# SignalProcessing.net
KiCad netlist of a schematic drawn in Altium Designer
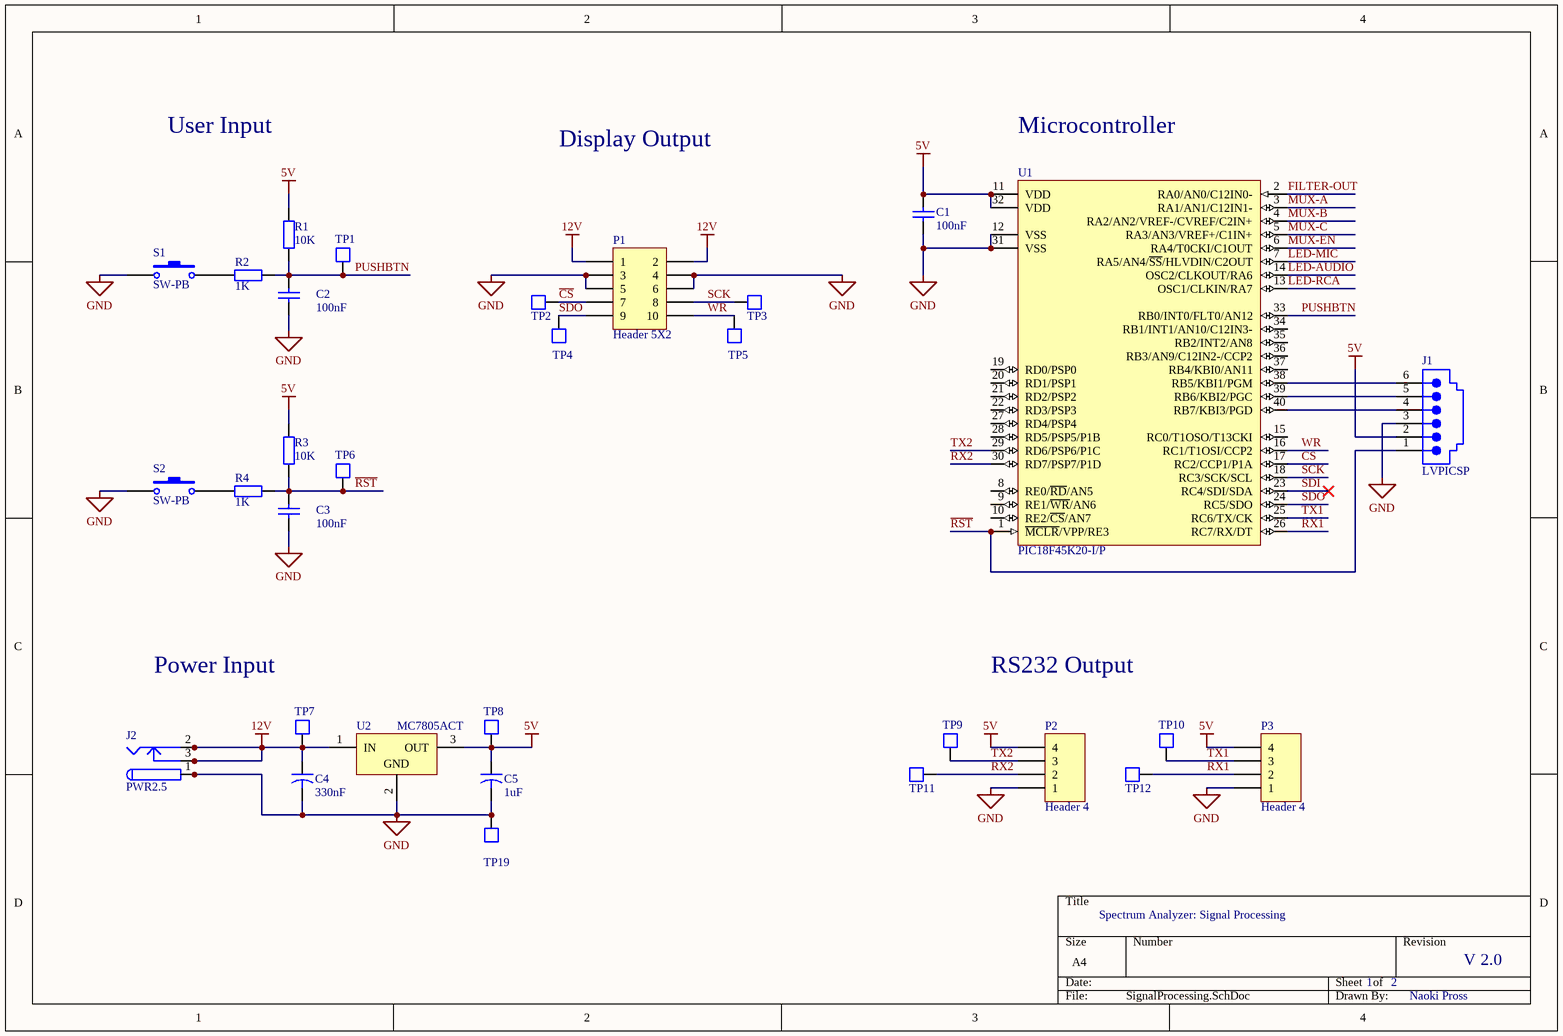
[diagram p0: SignalProcessing.SchDoc]

(export (version "E")
  (design (tool "Eeschema 10.0.6"))
  (components
    (comp (ref "C1")
      (value "100nF")
      (footprint "RAD-0.1")
      (description "Capacitor")
      (fields (field (name "Comment") "Cap") (field (name "PUBLISHER") "Altium Limited"))
      (libsource (lib "Miscellaneous Devices") (part "Cap"))
    )
    (comp (ref "C2")
      (value "100nF")
      (footprint "RAD-0.1")
      (description "Capacitor")
      (fields (field (name "Comment") "Cap") (field (name "PUBLISHER") "Altium Limited"))
      (libsource (lib "Miscellaneous Devices") (part "Cap"))
    )
    (comp (ref "C3")
      (value "100nF")
      (footprint "RAD-0.1")
      (description "Capacitor")
      (fields (field (name "Comment") "Cap") (field (name "PUBLISHER") "Altium Limited"))
      (libsource (lib "Miscellaneous Devices") (part "Cap"))
    )
    (comp (ref "C4")
      (value "330nF")
      (footprint "CAPR5-4X5")
      (description "Capacitor")
      (fields (field (name "Comment") "Cap2") (field (name "PUBLISHER") "Altium Limited"))
      (libsource (lib "Miscellaneous Devices") (part "Cap2"))
    )
    (comp (ref "C5")
      (value "1uF")
      (footprint "CAPR5-4X5")
      (description "Capacitor")
      (fields (field (name "Comment") "Cap2") (field (name "PUBLISHER") "Altium Limited"))
      (libsource (lib "Miscellaneous Devices") (part "Cap2"))
    )
    (comp (ref "J1")
      (value "LVPICSP")
      (footprint "95001-2661")
      (description "Right Angle, Low Profile, Flangeless PCB Jack")
      (fields (field (name "PUBLISHER") "Altium Limited"))
      (libsource (lib "Molex Modular Jack Right Angle") (part "95001-2661"))
    )
    (comp (ref "J2")
      (value "PWR2.5")
      (footprint "KLD-0202")
      (description "Low Voltage Power Supply Connector")
      (fields (field (name "PUBLISHER") "Altium Limited"))
      (libsource (lib "Miscellaneous Connectors") (part "PWR2.5"))
    )
    (comp (ref "P1")
      (value "Header 5X2")
      (footprint "HDR2X5")
      (description "Header, 5-Pin, Dual row")
      (fields (field (name "PUBLISHER") "Altium Limited"))
      (libsource (lib "Miscellaneous Connectors") (part "Header 5X2"))
    )
    (comp (ref "P2")
      (value "Header 4")
      (footprint "HDR1X4")
      (description "Header, 4-Pin")
      (fields (field (name "PUBLISHER") "Altium Limited"))
      (libsource (lib "Miscellaneous Connectors") (part "Header 4"))
    )
    (comp (ref "P3")
      (value "Header 4")
      (footprint "HDR1X4")
      (description "Header, 4-Pin")
      (fields (field (name "PUBLISHER") "Altium Limited"))
      (libsource (lib "Miscellaneous Connectors") (part "Header 4"))
    )
    (comp (ref "R1")
      (value "10K")
      (footprint "AXIAL-0.4")
      (description "Resistor")
      (fields (field (name "Comment") "Res2") (field (name "PUBLISHER") "Altium Limited"))
      (libsource (lib "") (part "Res2_1"))
    )
    (comp (ref "R2")
      (value "1K")
      (footprint "AXIAL-0.4")
      (description "Resistor")
      (fields (field (name "Comment") "Res2") (field (name "PUBLISHER") "Altium Limited"))
      (libsource (lib "Miscellaneous Devices") (part "Res2"))
    )
    (comp (ref "R3")
      (value "10K")
      (footprint "AXIAL-0.4")
      (description "Resistor")
      (fields (field (name "Comment") "Res2") (field (name "PUBLISHER") "Altium Limited"))
      (libsource (lib "") (part "Res2_1"))
    )
    (comp (ref "R4")
      (value "1K")
      (footprint "AXIAL-0.4")
      (description "Resistor")
      (fields (field (name "Comment") "Res2") (field (name "PUBLISHER") "Altium Limited"))
      (libsource (lib "Miscellaneous Devices") (part "Res2"))
    )
    (comp (ref "S1")
      (value "SW-PB")
      (footprint "PUSHBTN_12x12mm")
      (description "Switch")
      (fields (field (name "PUBLISHER") "Altium Limited"))
      (libsource (lib "Miscellaneous Devices") (part "SW-PB"))
    )
    (comp (ref "S2")
      (value "SW-PB")
      (footprint "PUSHBTN_6x6mm")
      (description "Switch")
      (fields (field (name "PUBLISHER") "Altium Limited"))
      (libsource (lib "Miscellaneous Devices") (part "SW-PB"))
    )
    (comp (ref "TP1") (value "Test Pad") (footprint "PIN1") (libsource (lib "TestPad") (part "TestPad")))
    (comp (ref "TP2") (value "Test Pad") (footprint "PIN1") (libsource (lib "TestPad") (part "TestPad")))
    (comp (ref "TP3") (value "Test Pad") (footprint "PIN1") (libsource (lib "TestPad") (part "TestPad")))
    (comp (ref "TP4") (value "Test Pad") (footprint "PIN1") (libsource (lib "TestPad") (part "TestPad")))
    (comp (ref "TP5") (value "Test Pad") (footprint "PIN1") (libsource (lib "TestPad") (part "TestPad")))
    (comp (ref "TP6") (value "Test Pad") (footprint "PIN1") (libsource (lib "TestPad") (part "TestPad")))
    (comp (ref "TP7") (value "Test Pad") (footprint "PIN1") (libsource (lib "TestPad") (part "TestPad")))
    (comp (ref "TP8") (value "Test Pad") (footprint "PIN1") (libsource (lib "TestPad") (part "TestPad")))
    (comp (ref "TP9") (value "Test Pad") (footprint "PIN1") (libsource (lib "TestPad") (part "TestPad")))
    (comp (ref "TP10") (value "Test Pad") (footprint "PIN1") (libsource (lib "TestPad") (part "TestPad")))
    (comp (ref "TP11") (value "Test Pad") (footprint "PIN1") (libsource (lib "TestPad") (part "TestPad")))
    (comp (ref "TP12") (value "Test Pad") (footprint "PIN1") (libsource (lib "TestPad") (part "TestPad")))
    (comp (ref "TP19") (value "Test Pad") (footprint "PIN1") (libsource (lib "TestPad") (part "TestPad")))
    (comp (ref "U1")
      (value "PIC18F45K20-I/P")
      (footprint "PDIP600-P40")
      (fields (field (name "PUBLISHER") "Altium Limited"))
      (libsource (lib "Microchip Microcontroller 8-Bit PIC18") (part "PIC18F45K20-I/P"))
    )
    (comp (ref "U2")
      (value "MC7805ACT")
      (footprint "221A-04")
      (description "3-Terminal Positive Fixed Voltage Regulator")
      (fields (field (name "PUBLISHER") "Altium Limited"))
      (libsource (lib "Motorola Power Mgt Voltage Regulator") (part "MC7805ACT"))
    )
  )
  (nets
    (net (code "1") (name "/FILTER-OUT") (class "Default")
      (node (ref "U1") (pin "2") (pinfunction "RA0/AN0/C12IN0-_2") (pintype "input"))
    )
    (net (code "2") (name "/LED-AUDIO") (class "Default")
      (node (ref "U1") (pin "14") (pinfunction "OSC2/CLKOUT/RA6_14") (pintype "bidirectional"))
    )
    (net (code "3") (name "/LED-MIC") (class "Default")
      (node (ref "U1") (pin "7") (pinfunction "RA5/AN4/~{SS}/HLVDIN/C2OUT_7") (pintype "bidirectional"))
    )
    (net (code "4") (name "/LED-RCA") (class "Default")
      (node (ref "U1") (pin "13") (pinfunction "OSC1/CLKIN/RA7_13") (pintype "bidirectional"))
    )
    (net (code "5") (name "/MUX-A") (class "Default")
      (node (ref "U1") (pin "3") (pinfunction "RA1/AN1/C12IN1-_3") (pintype "bidirectional"))
    )
    (net (code "6") (name "/MUX-B") (class "Default")
      (node (ref "U1") (pin "4") (pinfunction "RA2/AN2/VREF-/CVREF/C2IN+_4") (pintype "bidirectional"))
    )
    (net (code "7") (name "/MUX-C") (class "Default")
      (node (ref "U1") (pin "5") (pinfunction "RA3/AN3/VREF+/C1IN+_5") (pintype "bidirectional"))
    )
    (net (code "8") (name "/MUX-~{EN}") (class "Default")
      (node (ref "U1") (pin "6") (pinfunction "RA4/T0CKI/C1OUT_6") (pintype "bidirectional"))
    )
    (net (code "9") (name "/PUSHBTN") (class "Default")
      (node (ref "C2") (pin "2") (pinfunction "2_2") (pintype "passive"))
      (node (ref "R1") (pin "1") (pinfunction "1_1") (pintype "passive"))
      (node (ref "R2") (pin "2") (pinfunction "2_2") (pintype "passive"))
      (node (ref "TP1") (pin "1") (pinfunction "1_1") (pintype "passive"))
      (node (ref "U1") (pin "33") (pinfunction "RB0/INT0/FLT0/AN12_33") (pintype "bidirectional"))
    )
    (net (code "10") (name "/RX1") (class "Default")
      (node (ref "P3") (pin "2") (pinfunction "2_2") (pintype "passive"))
      (node (ref "TP12") (pin "1") (pinfunction "1_1") (pintype "passive"))
      (node (ref "U1") (pin "26") (pinfunction "RC7/RX/DT_26") (pintype "bidirectional"))
    )
    (net (code "11") (name "/RX2") (class "Default")
      (node (ref "P2") (pin "2") (pinfunction "2_2") (pintype "passive"))
      (node (ref "TP11") (pin "1") (pinfunction "1_1") (pintype "passive"))
      (node (ref "U1") (pin "30") (pinfunction "RD7/PSP7/P1D_30") (pintype "bidirectional"))
    )
    (net (code "12") (name "/SCK") (class "Default")
      (node (ref "P1") (pin "8") (pinfunction "8_8") (pintype "passive"))
      (node (ref "TP3") (pin "1") (pinfunction "1_1") (pintype "passive"))
      (node (ref "U1") (pin "18") (pinfunction "RC3/SCK/SCL_18") (pintype "bidirectional"))
    )
    (net (code "13") (name "/SDI") (class "Default")
      (node (ref "U1") (pin "23") (pinfunction "RC4/SDI/SDA_23") (pintype "bidirectional+no_connect"))
    )
    (net (code "14") (name "/SDO") (class "Default")
      (node (ref "P1") (pin "9") (pinfunction "9_9") (pintype "passive"))
      (node (ref "TP4") (pin "1") (pinfunction "1_1") (pintype "passive"))
      (node (ref "U1") (pin "24") (pinfunction "RC5/SDO_24") (pintype "bidirectional"))
    )
    (net (code "15") (name "/TX1") (class "Default")
      (node (ref "P3") (pin "3") (pinfunction "3_3") (pintype "passive"))
      (node (ref "TP10") (pin "1") (pinfunction "1_1") (pintype "passive"))
      (node (ref "U1") (pin "25") (pinfunction "RC6/TX/CK_25") (pintype "bidirectional"))
    )
    (net (code "16") (name "/TX2") (class "Default")
      (node (ref "P2") (pin "3") (pinfunction "3_3") (pintype "passive"))
      (node (ref "TP9") (pin "1") (pinfunction "1_1") (pintype "passive"))
      (node (ref "U1") (pin "29") (pinfunction "RD6/PSP6/P1C_29") (pintype "bidirectional"))
    )
    (net (code "17") (name "/WR") (class "Default")
      (node (ref "P1") (pin "10") (pinfunction "10_10") (pintype "passive"))
      (node (ref "TP5") (pin "1") (pinfunction "1_1") (pintype "passive"))
      (node (ref "U1") (pin "16") (pinfunction "RC1/T1OSI/CCP2_16") (pintype "bidirectional"))
    )
    (net (code "18") (name "/~{CS}") (class "Default")
      (node (ref "P1") (pin "7") (pinfunction "7_7") (pintype "passive"))
      (node (ref "TP2") (pin "1") (pinfunction "1_1") (pintype "passive"))
      (node (ref "U1") (pin "17") (pinfunction "RC2/CCP1/P1A_17") (pintype "bidirectional"))
    )
    (net (code "19") (name "/~{RST}") (class "Default")
      (node (ref "C3") (pin "2") (pinfunction "2_2") (pintype "passive"))
      (node (ref "J1") (pin "1") (pinfunction "1_1") (pintype "passive"))
      (node (ref "R3") (pin "1") (pinfunction "1_1") (pintype "passive"))
      (node (ref "R4") (pin "2") (pinfunction "2_2") (pintype "passive"))
      (node (ref "TP6") (pin "1") (pinfunction "1_1") (pintype "passive"))
      (node (ref "U1") (pin "1") (pinfunction "~{MCLR}/VPP/RE3_1") (pintype "input"))
    )
    (net (code "20") (name "5V") (class "Default")
      (node (ref "C1") (pin "1") (pinfunction "1_1") (pintype "passive"))
      (node (ref "C5") (pin "1") (pinfunction "1_1") (pintype "passive"))
      (node (ref "J1") (pin "2") (pinfunction "2_2") (pintype "passive"))
      (node (ref "P2") (pin "4") (pinfunction "4_4") (pintype "passive"))
      (node (ref "P3") (pin "4") (pinfunction "4_4") (pintype "passive"))
      (node (ref "R1") (pin "2") (pinfunction "2_2") (pintype "passive"))
      (node (ref "R3") (pin "2") (pinfunction "2_2") (pintype "passive"))
      (node (ref "TP8") (pin "1") (pinfunction "1_1") (pintype "passive"))
      (node (ref "U1") (pin "11") (pinfunction "VDD_11") (pintype "power_in"))
      (node (ref "U1") (pin "32") (pinfunction "VDD_32") (pintype "power_in"))
      (node (ref "U2") (pin "3") (pinfunction "OUT_3") (pintype "power_in"))
    )
    (net (code "21") (name "12V") (class "Default")
      (node (ref "C4") (pin "1") (pinfunction "1_1") (pintype "passive"))
      (node (ref "J2") (pin "2") (pinfunction "2_2") (pintype "power_in"))
      (node (ref "J2") (pin "2A") (pinfunction "2A_2A") (pintype "power_in"))
      (node (ref "J2") (pin "2B") (pinfunction "2B_2B") (pintype "power_in"))
      (node (ref "J2") (pin "3") (pinfunction "3_3") (pintype "power_in"))
      (node (ref "J2") (pin "3A") (pinfunction "3A_3A") (pintype "power_in"))
      (node (ref "J2") (pin "3B") (pinfunction "3B_3B") (pintype "power_in"))
      (node (ref "P1") (pin "1") (pinfunction "1_1") (pintype "passive"))
      (node (ref "P1") (pin "2") (pinfunction "2_2") (pintype "passive"))
      (node (ref "TP7") (pin "1") (pinfunction "1_1") (pintype "passive"))
      (node (ref "U2") (pin "1") (pinfunction "IN_1") (pintype "power_in"))
    )
    (net (code "22") (name "GND") (class "Default")
      (node (ref "C1") (pin "2") (pinfunction "2_2") (pintype "passive"))
      (node (ref "C2") (pin "1") (pinfunction "1_1") (pintype "passive"))
      (node (ref "C3") (pin "1") (pinfunction "1_1") (pintype "passive"))
      (node (ref "C4") (pin "2") (pinfunction "2_2") (pintype "passive"))
      (node (ref "C5") (pin "2") (pinfunction "2_2") (pintype "passive"))
      (node (ref "J1") (pin "3") (pinfunction "3_3") (pintype "passive"))
      (node (ref "J2") (pin "1") (pinfunction "1_1") (pintype "power_in"))
      (node (ref "J2") (pin "1A") (pinfunction "1A_1A") (pintype "power_in"))
      (node (ref "J2") (pin "1B") (pinfunction "1B_1B") (pintype "power_in"))
      (node (ref "P1") (pin "3") (pinfunction "3_3") (pintype "passive"))
      (node (ref "P1") (pin "4") (pinfunction "4_4") (pintype "passive"))
      (node (ref "P1") (pin "5") (pinfunction "5_5") (pintype "passive"))
      (node (ref "P1") (pin "6") (pinfunction "6_6") (pintype "passive"))
      (node (ref "P2") (pin "1") (pinfunction "1_1") (pintype "passive"))
      (node (ref "P3") (pin "1") (pinfunction "1_1") (pintype "passive"))
      (node (ref "S1") (pin "1") (pinfunction "1_1") (pintype "passive"))
      (node (ref "S2") (pin "1") (pinfunction "1_1") (pintype "passive"))
      (node (ref "TP19") (pin "1") (pinfunction "1_1") (pintype "passive"))
      (node (ref "U1") (pin "12") (pinfunction "VSS_12") (pintype "power_in"))
      (node (ref "U1") (pin "31") (pinfunction "VSS_31") (pintype "power_in"))
      (node (ref "U2") (pin "2") (pinfunction "GND_2") (pintype "power_in"))
    )
    (net (code "23") (name "Net-(R2-Pad1)") (class "Default")
      (node (ref "R2") (pin "1") (pinfunction "1_1") (pintype "passive"))
      (node (ref "S1") (pin "2") (pinfunction "2_2") (pintype "passive"))
    )
    (net (code "24") (name "Net-(R4-Pad1)") (class "Default")
      (node (ref "R4") (pin "1") (pinfunction "1_1") (pintype "passive"))
      (node (ref "S2") (pin "2") (pinfunction "2_2") (pintype "passive"))
    )
    (net (code "25") (name "Net-(U1-RB5{slash}KBI1{slash}PGM)") (class "Default")
      (node (ref "J1") (pin "6") (pinfunction "6_6") (pintype "passive"))
      (node (ref "U1") (pin "38") (pinfunction "RB5/KBI1/PGM_38") (pintype "bidirectional"))
    )
    (net (code "26") (name "Net-(U1-RB6{slash}KBI2{slash}PGC)") (class "Default")
      (node (ref "J1") (pin "5") (pinfunction "5_5") (pintype "passive"))
      (node (ref "U1") (pin "39") (pinfunction "RB6/KBI2/PGC_39") (pintype "bidirectional"))
    )
    (net (code "27") (name "Net-(U1-RB7{slash}KBI3{slash}PGD)") (class "Default")
      (node (ref "J1") (pin "4") (pinfunction "4_4") (pintype "passive"))
      (node (ref "U1") (pin "40") (pinfunction "RB7/KBI3/PGD_40") (pintype "bidirectional"))
    )
    (net (code "28") (name "unconnected-(U1-RB1{slash}INT1{slash}AN10{slash}C12IN3--Pad34)") (class "Default")
      (node (ref "U1") (pin "34") (pinfunction "RB1/INT1/AN10/C12IN3-_34") (pintype "bidirectional"))
    )
    (net (code "29") (name "unconnected-(U1-RB2{slash}INT2{slash}AN8-Pad35)") (class "Default")
      (node (ref "U1") (pin "35") (pinfunction "RB2/INT2/AN8_35") (pintype "bidirectional"))
    )
    (net (code "30") (name "unconnected-(U1-RB3{slash}AN9{slash}C12IN2-{slash}CCP2-Pad36)") (class "Default")
      (node (ref "U1") (pin "36") (pinfunction "RB3/AN9/C12IN2-/CCP2_36") (pintype "bidirectional"))
    )
    (net (code "31") (name "unconnected-(U1-RB4{slash}KBI0{slash}AN11-Pad37)") (class "Default")
      (node (ref "U1") (pin "37") (pinfunction "RB4/KBI0/AN11_37") (pintype "bidirectional"))
    )
    (net (code "32") (name "unconnected-(U1-RC0{slash}T1OSO{slash}T13CKI-Pad15)") (class "Default")
      (node (ref "U1") (pin "15") (pinfunction "RC0/T1OSO/T13CKI_15") (pintype "bidirectional"))
    )
    (net (code "33") (name "unconnected-(U1-RD0{slash}PSP0-Pad19)") (class "Default")
      (node (ref "U1") (pin "19") (pinfunction "RD0/PSP0_19") (pintype "bidirectional"))
    )
    (net (code "34") (name "unconnected-(U1-RD1{slash}PSP1-Pad20)") (class "Default")
      (node (ref "U1") (pin "20") (pinfunction "RD1/PSP1_20") (pintype "bidirectional"))
    )
    (net (code "35") (name "unconnected-(U1-RD2{slash}PSP2-Pad21)") (class "Default")
      (node (ref "U1") (pin "21") (pinfunction "RD2/PSP2_21") (pintype "bidirectional"))
    )
    (net (code "36") (name "unconnected-(U1-RD3{slash}PSP3-Pad22)") (class "Default")
      (node (ref "U1") (pin "22") (pinfunction "RD3/PSP3_22") (pintype "bidirectional"))
    )
    (net (code "37") (name "unconnected-(U1-RD4{slash}PSP4-Pad27)") (class "Default")
      (node (ref "U1") (pin "27") (pinfunction "RD4/PSP4_27") (pintype "bidirectional"))
    )
    (net (code "38") (name "unconnected-(U1-RD5{slash}PSP5{slash}P1B-Pad28)") (class "Default")
      (node (ref "U1") (pin "28") (pinfunction "RD5/PSP5/P1B_28") (pintype "bidirectional"))
    )
    (net (code "39") (name "unconnected-(U1-RE0{slash}~{RD}{slash}AN5-Pad8)") (class "Default")
      (node (ref "U1") (pin "8") (pinfunction "RE0/~{RD}/AN5_8") (pintype "bidirectional"))
    )
    (net (code "40") (name "unconnected-(U1-RE1{slash}~{WR}{slash}AN6-Pad9)") (class "Default")
      (node (ref "U1") (pin "9") (pinfunction "RE1/~{WR}/AN6_9") (pintype "bidirectional"))
    )
    (net (code "41") (name "unconnected-(U1-RE2{slash}~{CS}{slash}AN7-Pad10)") (class "Default")
      (node (ref "U1") (pin "10") (pinfunction "RE2/~{CS}/AN7_10") (pintype "bidirectional"))
    )
  )
)
